# POWER.net
KiCad netlist of a schematic drawn in Altium Designer
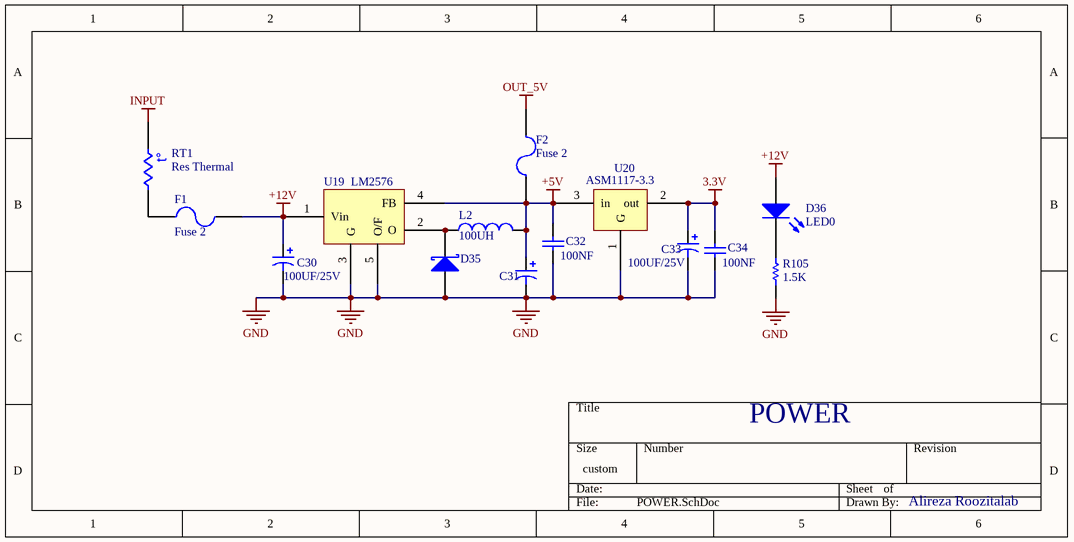
[diagram p0: POWER.SchDoc]

(export (version "E")
  (design (tool "Eeschema 10.0.6"))
  (components
    (comp (ref "C30")
      (value "100UF/25V")
      (footprint "POL 220U/35V")
      (description "Polarized Capacitor (Radial)")
      (fields (field (name "Comment") "Cap Pol1") (field (name "PUBLISHER") "Altium Limited"))
      (libsource (lib "Miscellaneous Devices") (part "Cap Pol1"))
    )
    (comp (ref "C31")
      (value "Cap Pol1")
      (footprint "POL 220U/35V")
      (description "Polarized Capacitor (Radial)")
      (fields (field (name "PUBLISHER") "Altium Limited"))
      (libsource (lib "Miscellaneous Devices") (part "Cap Pol1"))
    )
    (comp (ref "C32")
      (value "100NF")
      (footprint "REC 10N")
      (description "Capacitor")
      (fields (field (name "Comment") "Cap") (field (name "PUBLISHER") "Altium Limited"))
      (libsource (lib "Miscellaneous Devices") (part "Cap"))
    )
    (comp (ref "C33")
      (value "100UF/25V")
      (footprint "POL 100U/25V")
      (description "Polarized Capacitor (Radial)")
      (fields (field (name "Comment") "Cap Pol1") (field (name "PUBLISHER") "Altium Limited"))
      (libsource (lib "Miscellaneous Devices") (part "Cap Pol1"))
    )
    (comp (ref "C34")
      (value "100NF")
      (footprint "REC 10N")
      (description "Capacitor")
      (fields (field (name "Comment") "Cap") (field (name "PUBLISHER") "Altium Limited"))
      (libsource (lib "Miscellaneous Devices") (part "Cap"))
    )
    (comp (ref "D35")
      (value "D Schottky")
      (footprint "DO214AC")
      (description "Schottky Diode")
      (fields (field (name "PUBLISHER") "Altium Limited"))
      (libsource (lib "Miscellaneous Devices") (part "D Schottky"))
    )
    (comp (ref "D36")
      (value "LED0")
      (footprint "led-1206")
      (description "Typical INFRARED GaAs LED")
      (fields (field (name "PUBLISHER") "Altium Limited"))
      (libsource (lib "Miscellaneous Devices") (part "LED0"))
    )
    (comp (ref "F1")
      (value "Fuse 2")
      (footprint "fuse plastic holder")
      (description "Fuse")
      (fields (field (name "PUBLISHER") "Altium Limited"))
      (libsource (lib "Miscellaneous Devices") (part "Fuse 2"))
    )
    (comp (ref "F2")
      (value "Fuse 2")
      (footprint "fuse plastic holder")
      (description "Fuse")
      (fields (field (name "PUBLISHER") "Altium Limited"))
      (libsource (lib "Miscellaneous Devices") (part "Fuse 2"))
    )
    (comp (ref "L2")
      (value "100UH")
      (footprint "TR")
      (description "Inductor")
      (fields (field (name "PUBLISHER") "Altium Limited"))
      (libsource (lib "Miscellaneous Devices") (part "Inductor"))
    )
    (comp (ref "R105")
      (value "1.5K")
      (footprint "RES 1206 (3216X08L)")
      (description "Resistor")
      (fields (field (name "Comment") "Res1") (field (name "PUBLISHER") "Altium Limited"))
      (libsource (lib "Miscellaneous Devices") (part "Res1"))
    )
    (comp (ref "RT1")
      (value "Res Thermal")
      (footprint "Varistor Short Hieght - Vertical")
      (description "Thermistor")
      (fields (field (name "PUBLISHER") "Altium Limited"))
      (libsource (lib "Miscellaneous Devices") (part "Res Thermal"))
    )
    (comp (ref "U19") (value "LM2576") (footprint "d2pak5-lead") (libsource (lib "LPC") (part "LM2576-5V")))
    (comp (ref "U20")
      (value "ASM1117-3.3")
      (footprint "SOT-223")
      (libsource (lib "LPC") (part "ASM1117-3.3"))
    )
  )
  (nets
    (net (code "1") (name "+5V") (class "Default")
      (node (ref "C31") (pin "1") (pinfunction "1_1") (pintype "passive"))
      (node (ref "C32") (pin "2") (pinfunction "2_2") (pintype "passive"))
      (node (ref "F2") (pin "1") (pinfunction "1_1") (pintype "passive"))
      (node (ref "L2") (pin "2") (pinfunction "2_2") (pintype "passive"))
      (node (ref "U19") (pin "4") (pinfunction "FB_4") (pintype "passive"))
      (node (ref "U20") (pin "3") (pinfunction "in_3") (pintype "passive"))
    )
    (net (code "2") (name "+12V") (class "Default")
      (node (ref "C30") (pin "1") (pinfunction "1_1") (pintype "passive"))
      (node (ref "D36") (pin "1") (pinfunction "A_1") (pintype "passive"))
      (node (ref "F1") (pin "2") (pinfunction "2_2") (pintype "passive"))
      (node (ref "U19") (pin "1") (pinfunction "Vin_1") (pintype "passive"))
    )
    (net (code "3") (name "3.3V") (class "Default")
      (node (ref "C33") (pin "1") (pinfunction "1_1") (pintype "passive"))
      (node (ref "C34") (pin "2") (pinfunction "2_2") (pintype "passive"))
      (node (ref "U20") (pin "2") (pinfunction "out_2") (pintype "passive"))
    )
    (net (code "4") (name "GND") (class "Default")
      (node (ref "C30") (pin "2") (pinfunction "2_2") (pintype "passive"))
      (node (ref "C31") (pin "2") (pinfunction "2_2") (pintype "passive"))
      (node (ref "C32") (pin "1") (pinfunction "1_1") (pintype "passive"))
      (node (ref "C33") (pin "2") (pinfunction "2_2") (pintype "passive"))
      (node (ref "C34") (pin "1") (pinfunction "1_1") (pintype "passive"))
      (node (ref "D35") (pin "1") (pinfunction "A_1") (pintype "passive"))
      (node (ref "R105") (pin "1") (pinfunction "1_1") (pintype "passive"))
      (node (ref "U19") (pin "3") (pinfunction "G_3") (pintype "passive"))
      (node (ref "U19") (pin "5") (pinfunction "O/F_5") (pintype "passive"))
      (node (ref "U20") (pin "1") (pinfunction "G_1") (pintype "passive"))
    )
    (net (code "5") (name "INPUT") (class "Default")
      (node (ref "RT1") (pin "1") (pinfunction "1_1") (pintype "passive"))
    )
    (net (code "6") (name "Net-(D35-K)") (class "Default")
      (node (ref "D35") (pin "2") (pinfunction "K_2") (pintype "passive"))
      (node (ref "L2") (pin "1") (pinfunction "1_1") (pintype "passive"))
      (node (ref "U19") (pin "2") (pinfunction "O_2") (pintype "passive"))
    )
    (net (code "7") (name "Net-(D36-K)") (class "Default")
      (node (ref "D36") (pin "2") (pinfunction "K_2") (pintype "passive"))
      (node (ref "R105") (pin "2") (pinfunction "2_2") (pintype "passive"))
    )
    (net (code "8") (name "Net-(F1-Pad1)") (class "Default")
      (node (ref "F1") (pin "1") (pinfunction "1_1") (pintype "passive"))
      (node (ref "RT1") (pin "2") (pinfunction "2_2") (pintype "passive"))
    )
    (net (code "9") (name "OUT_5V") (class "Default")
      (node (ref "F2") (pin "2") (pinfunction "2_2") (pintype "passive"))
    )
  )
)
